# Sheet1.net
KiCad netlist of a schematic drawn in Altium Designer
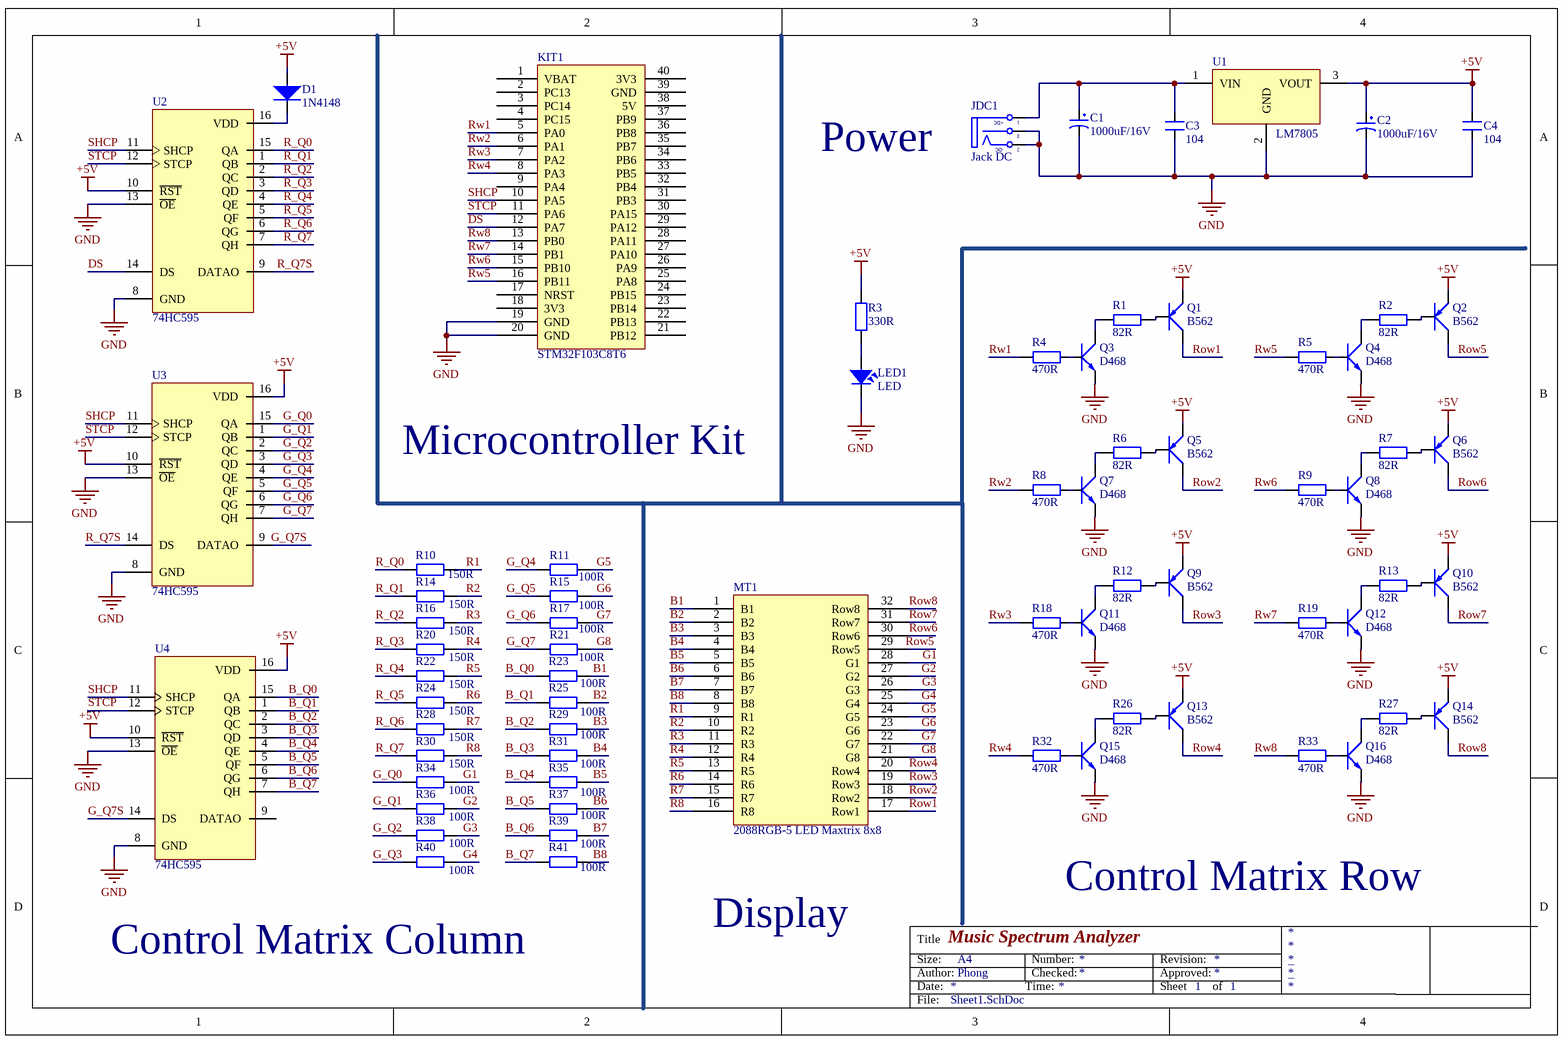
[diagram p0: Sheet1.SchDoc]

(export (version "E")
  (design (tool "Eeschema 10.0.6"))
  (components
    (comp (ref "C1")
      (value "1000uF/16V")
      (footprint "CP1.5/3.4")
      (description "Cap 1000uF/16V - 220uF/50V")
      (libsource (lib "KhanhBK_Library_4") (part "CP4"))
    )
    (comp (ref "C2")
      (value "1000uF/16V")
      (footprint "CP1.5/3.4")
      (description "Cap 1000uF/16V - 220uF/50V")
      (libsource (lib "KhanhBK_Library_4") (part "CP4"))
    )
    (comp (ref "C3")
      (value "104")
      (footprint "CN2")
      (description "Cap np 104 => 105pF")
      (libsource (lib "KhanhBK_SCH_Library_2") (part "CN2"))
    )
    (comp (ref "C4")
      (value "104")
      (footprint "CN2")
      (description "Cap np 104 => 105pF")
      (libsource (lib "KhanhBK_SCH_Library_2") (part "CN2"))
    )
    (comp (ref "D1")
      (value "1N4148")
      (footprint "DO-35")
      (description "Diode Standard")
      (fields (field (name "PART NUMBER") "LED 3 ly Single Colour"))
      (libsource (lib "KhanhBK_Library_4") (part "Diode Standard"))
    )
    (comp (ref "JDC1")
      (value "Jack DC")
      (footprint "DC-IN")
      (description "Jac DC input")
      (libsource (lib "KhanhBK_SCH_Library_2") (part "DCIN"))
    )
    (comp (ref "KIT1")
      (value "STM32F103C8T6")
      (footprint "STM32F103C8T6 BLUE PILL DEVELOPMENT BOARD")
      (description "STM32F103C8T6 Blue Pill Development Board")
      (libsource (lib "Schlib1") (part "Kit STM32F103C8T6 blue pill"))
    )
    (comp (ref "LED1")
      (value "LED")
      (footprint "LED-3")
      (description "LED Single colour Green and Red")
      (libsource (lib "KhanhBK_SCH_Library_2") (part "LED"))
    )
    (comp (ref "MT1")
      (value "2088RGB-5 LED Maxtrix 8x8")
      (footprint "LED 8x8 RGB")
      (description "32 pins")
      (libsource (lib "Schlib1") (part "LED 8x8 RGB"))
    )
    (comp (ref "Q1")
      (value "B562")
      (footprint "QTO-92")
      (description "P 600mW, ECB")
      (libsource (lib "KhanhBK_SCH_Library_2") (part "PNP_ECB"))
    )
    (comp (ref "Q2")
      (value "B562")
      (footprint "QTO-92")
      (description "P 600mW, ECB")
      (libsource (lib "KhanhBK_SCH_Library_2") (part "PNP_ECB"))
    )
    (comp (ref "Q3")
      (value "D468")
      (footprint "QTO-92")
      (description "P 600mW, ECB")
      (libsource (lib "KhanhBK_SCH_Library_2") (part "NPN_ECB"))
    )
    (comp (ref "Q4")
      (value "D468")
      (footprint "QTO-92")
      (description "P 600mW, ECB")
      (libsource (lib "KhanhBK_SCH_Library_2") (part "NPN_ECB"))
    )
    (comp (ref "Q5")
      (value "B562")
      (footprint "QTO-92")
      (description "P 600mW, ECB")
      (libsource (lib "KhanhBK_SCH_Library_2") (part "PNP_ECB"))
    )
    (comp (ref "Q6")
      (value "B562")
      (footprint "QTO-92")
      (description "P 600mW, ECB")
      (libsource (lib "KhanhBK_SCH_Library_2") (part "PNP_ECB"))
    )
    (comp (ref "Q7")
      (value "D468")
      (footprint "QTO-92")
      (description "P 600mW, ECB")
      (libsource (lib "KhanhBK_SCH_Library_2") (part "NPN_ECB"))
    )
    (comp (ref "Q8")
      (value "D468")
      (footprint "QTO-92")
      (description "P 600mW, ECB")
      (libsource (lib "KhanhBK_SCH_Library_2") (part "NPN_ECB"))
    )
    (comp (ref "Q9")
      (value "B562")
      (footprint "QTO-92")
      (description "P 600mW, ECB")
      (libsource (lib "KhanhBK_SCH_Library_2") (part "PNP_ECB"))
    )
    (comp (ref "Q10")
      (value "B562")
      (footprint "QTO-92")
      (description "P 600mW, ECB")
      (libsource (lib "KhanhBK_SCH_Library_2") (part "PNP_ECB"))
    )
    (comp (ref "Q11")
      (value "D468")
      (footprint "QTO-92")
      (description "P 600mW, ECB")
      (libsource (lib "KhanhBK_SCH_Library_2") (part "NPN_ECB"))
    )
    (comp (ref "Q12")
      (value "D468")
      (footprint "QTO-92")
      (description "P 600mW, ECB")
      (libsource (lib "KhanhBK_SCH_Library_2") (part "NPN_ECB"))
    )
    (comp (ref "Q13")
      (value "B562")
      (footprint "QTO-92")
      (description "P 600mW, ECB")
      (libsource (lib "KhanhBK_SCH_Library_2") (part "PNP_ECB"))
    )
    (comp (ref "Q14")
      (value "B562")
      (footprint "QTO-92")
      (description "P 600mW, ECB")
      (libsource (lib "KhanhBK_SCH_Library_2") (part "PNP_ECB"))
    )
    (comp (ref "Q15")
      (value "D468")
      (footprint "QTO-92")
      (description "P 600mW, ECB")
      (libsource (lib "KhanhBK_SCH_Library_2") (part "NPN_ECB"))
    )
    (comp (ref "Q16")
      (value "D468")
      (footprint "QTO-92")
      (description "P 600mW, ECB")
      (libsource (lib "KhanhBK_SCH_Library_2") (part "NPN_ECB"))
    )
    (comp (ref "R1")
      (value "82R")
      (footprint "RES-1/4W-SMALL")
      (description "Resistor 1/4W")
      (libsource (lib "KhanhBK_SCH_Library_2") (part "RES 1/4W"))
    )
    (comp (ref "R2")
      (value "82R")
      (footprint "RES-1/4W-SMALL")
      (description "Resistor 1/4W")
      (libsource (lib "KhanhBK_SCH_Library_2") (part "RES 1/4W"))
    )
    (comp (ref "R3")
      (value "330R")
      (footprint "RES-1/4W-SMALL")
      (description "Resistor 1/4W")
      (libsource (lib "KhanhBK_SCH_Library_2") (part "RES 1/4W"))
    )
    (comp (ref "R4")
      (value "470R")
      (footprint "RES-1/4W-SMALL")
      (description "Resistor 1/4W")
      (libsource (lib "KhanhBK_SCH_Library_2") (part "RES 1/4W"))
    )
    (comp (ref "R5")
      (value "470R")
      (footprint "RES-1/4W-SMALL")
      (description "Resistor 1/4W")
      (libsource (lib "KhanhBK_SCH_Library_2") (part "RES 1/4W"))
    )
    (comp (ref "R6")
      (value "82R")
      (footprint "RES-1/4W-SMALL")
      (description "Resistor 1/4W")
      (libsource (lib "KhanhBK_SCH_Library_2") (part "RES 1/4W"))
    )
    (comp (ref "R7")
      (value "82R")
      (footprint "RES-1/4W-SMALL")
      (description "Resistor 1/4W")
      (libsource (lib "KhanhBK_SCH_Library_2") (part "RES 1/4W"))
    )
    (comp (ref "R8")
      (value "470R")
      (footprint "RES-1/4W-SMALL")
      (description "Resistor 1/4W")
      (libsource (lib "KhanhBK_SCH_Library_2") (part "RES 1/4W"))
    )
    (comp (ref "R9")
      (value "470R")
      (footprint "RES-1/4W-SMALL")
      (description "Resistor 1/4W")
      (libsource (lib "KhanhBK_SCH_Library_2") (part "RES 1/4W"))
    )
    (comp (ref "R10")
      (value "150R")
      (footprint "RES-1/4W-SMALL")
      (description "Resistor 1/4W")
      (libsource (lib "KhanhBK_SCH_Library_2") (part "RES 1/4W"))
    )
    (comp (ref "R11")
      (value "100R")
      (footprint "RES-1/4W-SMALL")
      (description "Resistor 1/4W")
      (libsource (lib "KhanhBK_SCH_Library_2") (part "RES 1/4W"))
    )
    (comp (ref "R12")
      (value "82R")
      (footprint "RES-1/4W-SMALL")
      (description "Resistor 1/4W")
      (libsource (lib "KhanhBK_SCH_Library_2") (part "RES 1/4W"))
    )
    (comp (ref "R13")
      (value "82R")
      (footprint "RES-1/4W-SMALL")
      (description "Resistor 1/4W")
      (libsource (lib "KhanhBK_SCH_Library_2") (part "RES 1/4W"))
    )
    (comp (ref "R14")
      (value "150R")
      (footprint "RES-1/4W-SMALL")
      (description "Resistor 1/4W")
      (libsource (lib "KhanhBK_SCH_Library_2") (part "RES 1/4W"))
    )
    (comp (ref "R15")
      (value "100R")
      (footprint "RES-1/4W-SMALL")
      (description "Resistor 1/4W")
      (libsource (lib "KhanhBK_SCH_Library_2") (part "RES 1/4W"))
    )
    (comp (ref "R16")
      (value "150R")
      (footprint "RES-1/4W-SMALL")
      (description "Resistor 1/4W")
      (libsource (lib "KhanhBK_SCH_Library_2") (part "RES 1/4W"))
    )
    (comp (ref "R17")
      (value "100R")
      (footprint "RES-1/4W-SMALL")
      (description "Resistor 1/4W")
      (libsource (lib "KhanhBK_SCH_Library_2") (part "RES 1/4W"))
    )
    (comp (ref "R18")
      (value "470R")
      (footprint "RES-1/4W-SMALL")
      (description "Resistor 1/4W")
      (libsource (lib "KhanhBK_SCH_Library_2") (part "RES 1/4W"))
    )
    (comp (ref "R19")
      (value "470R")
      (footprint "RES-1/4W-SMALL")
      (description "Resistor 1/4W")
      (libsource (lib "KhanhBK_SCH_Library_2") (part "RES 1/4W"))
    )
    (comp (ref "R20")
      (value "150R")
      (footprint "RES-1/4W-SMALL")
      (description "Resistor 1/4W")
      (libsource (lib "KhanhBK_SCH_Library_2") (part "RES 1/4W"))
    )
    (comp (ref "R21")
      (value "100R")
      (footprint "RES-1/4W-SMALL")
      (description "Resistor 1/4W")
      (libsource (lib "KhanhBK_SCH_Library_2") (part "RES 1/4W"))
    )
    (comp (ref "R22")
      (value "150R")
      (footprint "RES-1/4W-SMALL")
      (description "Resistor 1/4W")
      (libsource (lib "KhanhBK_SCH_Library_2") (part "RES 1/4W"))
    )
    (comp (ref "R23")
      (value "100R")
      (footprint "RES-1/4W-SMALL")
      (description "Resistor 1/4W")
      (libsource (lib "KhanhBK_SCH_Library_2") (part "RES 1/4W"))
    )
    (comp (ref "R24")
      (value "150R")
      (footprint "RES-1/4W-SMALL")
      (description "Resistor 1/4W")
      (libsource (lib "KhanhBK_SCH_Library_2") (part "RES 1/4W"))
    )
    (comp (ref "R25")
      (value "100R")
      (footprint "RES-1/4W-SMALL")
      (description "Resistor 1/4W")
      (libsource (lib "KhanhBK_SCH_Library_2") (part "RES 1/4W"))
    )
    (comp (ref "R26")
      (value "82R")
      (footprint "RES-1/4W-SMALL")
      (description "Resistor 1/4W")
      (libsource (lib "KhanhBK_SCH_Library_2") (part "RES 1/4W"))
    )
    (comp (ref "R27")
      (value "82R")
      (footprint "RES-1/4W-SMALL")
      (description "Resistor 1/4W")
      (libsource (lib "KhanhBK_SCH_Library_2") (part "RES 1/4W"))
    )
    (comp (ref "R28")
      (value "150R")
      (footprint "RES-1/4W-SMALL")
      (description "Resistor 1/4W")
      (libsource (lib "KhanhBK_SCH_Library_2") (part "RES 1/4W"))
    )
    (comp (ref "R29")
      (value "100R")
      (footprint "RES-1/4W-SMALL")
      (description "Resistor 1/4W")
      (libsource (lib "KhanhBK_SCH_Library_2") (part "RES 1/4W"))
    )
    (comp (ref "R30")
      (value "150R")
      (footprint "RES-1/4W-SMALL")
      (description "Resistor 1/4W")
      (libsource (lib "KhanhBK_SCH_Library_2") (part "RES 1/4W"))
    )
    (comp (ref "R31")
      (value "100R")
      (footprint "RES-1/4W-SMALL")
      (description "Resistor 1/4W")
      (libsource (lib "KhanhBK_SCH_Library_2") (part "RES 1/4W"))
    )
    (comp (ref "R32")
      (value "470R")
      (footprint "RES-1/4W-SMALL")
      (description "Resistor 1/4W")
      (libsource (lib "KhanhBK_SCH_Library_2") (part "RES 1/4W"))
    )
    (comp (ref "R33")
      (value "470R")
      (footprint "RES-1/4W-SMALL")
      (description "Resistor 1/4W")
      (libsource (lib "KhanhBK_SCH_Library_2") (part "RES 1/4W"))
    )
    (comp (ref "R34")
      (value "100R")
      (footprint "RES-1/4W-SMALL")
      (description "Resistor 1/4W")
      (libsource (lib "KhanhBK_SCH_Library_2") (part "RES 1/4W"))
    )
    (comp (ref "R35")
      (value "100R")
      (footprint "RES-1/4W-SMALL")
      (description "Resistor 1/4W")
      (libsource (lib "KhanhBK_SCH_Library_2") (part "RES 1/4W"))
    )
    (comp (ref "R36")
      (value "100R")
      (footprint "RES-1/4W-SMALL")
      (description "Resistor 1/4W")
      (libsource (lib "KhanhBK_SCH_Library_2") (part "RES 1/4W"))
    )
    (comp (ref "R37")
      (value "100R")
      (footprint "RES-1/4W-SMALL")
      (description "Resistor 1/4W")
      (libsource (lib "KhanhBK_SCH_Library_2") (part "RES 1/4W"))
    )
    (comp (ref "R38")
      (value "100R")
      (footprint "RES-1/4W-SMALL")
      (description "Resistor 1/4W")
      (libsource (lib "KhanhBK_SCH_Library_2") (part "RES 1/4W"))
    )
    (comp (ref "R39")
      (value "100R")
      (footprint "RES-1/4W-SMALL")
      (description "Resistor 1/4W")
      (libsource (lib "KhanhBK_SCH_Library_2") (part "RES 1/4W"))
    )
    (comp (ref "R40")
      (value "100R")
      (footprint "RES-1/4W-SMALL")
      (description "Resistor 1/4W")
      (libsource (lib "KhanhBK_SCH_Library_2") (part "RES 1/4W"))
    )
    (comp (ref "R41")
      (value "100R")
      (footprint "RES-1/4W-SMALL")
      (description "Resistor 1/4W")
      (libsource (lib "KhanhBK_SCH_Library_2") (part "RES 1/4W"))
    )
    (comp (ref "U1")
      (value "LM7805")
      (footprint "Library:TO220H3")
      (libsource (lib "KhanhBK_SCH_Lib_5") (part "LM7815"))
    )
    (comp (ref "U2")
      (value "74HC595")
      (footprint "DIP16")
      (description "8-Bit Serial-Input/Serial or Prallel-Output Shift Register with Latched 3-State Outputs")
      (fields (field (name "PUBLISHER") "Altium Limited"))
      (libsource (lib "Devzone_SCHLib") (part "74HC595"))
    )
    (comp (ref "U3")
      (value "74HC595")
      (footprint "DIP16")
      (description "8-Bit Serial-Input/Serial or Prallel-Output Shift Register with Latched 3-State Outputs")
      (fields (field (name "PUBLISHER") "Altium Limited"))
      (libsource (lib "Devzone_SCHLib") (part "74HC595"))
    )
    (comp (ref "U4")
      (value "74HC595")
      (footprint "DIP16")
      (description "8-Bit Serial-Input/Serial or Prallel-Output Shift Register with Latched 3-State Outputs")
      (fields (field (name "PUBLISHER") "Altium Limited"))
      (libsource (lib "Devzone_SCHLib") (part "74HC595"))
    )
  )
  (nets
    (net (code "1") (name "+5V") (class "Default")
      (node (ref "C2") (pin "1") (pinfunction "1_1") (pintype "passive"))
      (node (ref "C4") (pin "2") (pinfunction "2_2") (pintype "passive"))
      (node (ref "D1") (pin "1") (pinfunction "1_1") (pintype "passive"))
      (node (ref "Q1") (pin "1") (pinfunction "E_1") (pintype "passive"))
      (node (ref "Q10") (pin "1") (pinfunction "E_1") (pintype "passive"))
      (node (ref "Q13") (pin "1") (pinfunction "E_1") (pintype "passive"))
      (node (ref "Q14") (pin "1") (pinfunction "E_1") (pintype "passive"))
      (node (ref "Q2") (pin "1") (pinfunction "E_1") (pintype "passive"))
      (node (ref "Q5") (pin "1") (pinfunction "E_1") (pintype "passive"))
      (node (ref "Q6") (pin "1") (pinfunction "E_1") (pintype "passive"))
      (node (ref "Q9") (pin "1") (pinfunction "E_1") (pintype "passive"))
      (node (ref "R3") (pin "2") (pinfunction "2_2") (pintype "passive"))
      (node (ref "U1") (pin "3") (pinfunction "VOUT_3") (pintype "passive"))
      (node (ref "U2") (pin "10") (pinfunction "~{RST}_10") (pintype "passive"))
      (node (ref "U3") (pin "10") (pinfunction "~{RST}_10") (pintype "passive"))
      (node (ref "U3") (pin "16") (pinfunction "VDD_16") (pintype "power_in"))
      (node (ref "U4") (pin "10") (pinfunction "~{RST}_10") (pintype "passive"))
      (node (ref "U4") (pin "16") (pinfunction "VDD_16") (pintype "power_in"))
    )
    (net (code "2") (name "/B1") (class "Default")
      (node (ref "MT1") (pin "1") (pinfunction "B1_1") (pintype "passive"))
      (node (ref "R23") (pin "2") (pinfunction "2_2") (pintype "passive"))
    )
    (net (code "3") (name "/B2") (class "Default")
      (node (ref "MT1") (pin "2") (pinfunction "B2_2") (pintype "passive"))
      (node (ref "R25") (pin "2") (pinfunction "2_2") (pintype "passive"))
    )
    (net (code "4") (name "/B3") (class "Default")
      (node (ref "MT1") (pin "3") (pinfunction "B3_3") (pintype "passive"))
      (node (ref "R29") (pin "2") (pinfunction "2_2") (pintype "passive"))
    )
    (net (code "5") (name "/B4") (class "Default")
      (node (ref "MT1") (pin "4") (pinfunction "B4_4") (pintype "passive"))
      (node (ref "R31") (pin "2") (pinfunction "2_2") (pintype "passive"))
    )
    (net (code "6") (name "/B5") (class "Default")
      (node (ref "MT1") (pin "5") (pinfunction "B5_5") (pintype "passive"))
      (node (ref "R35") (pin "2") (pinfunction "2_2") (pintype "passive"))
    )
    (net (code "7") (name "/B6") (class "Default")
      (node (ref "MT1") (pin "6") (pinfunction "B6_6") (pintype "passive"))
      (node (ref "R37") (pin "2") (pinfunction "2_2") (pintype "passive"))
    )
    (net (code "8") (name "/B7") (class "Default")
      (node (ref "MT1") (pin "7") (pinfunction "B7_7") (pintype "passive"))
      (node (ref "R39") (pin "2") (pinfunction "2_2") (pintype "passive"))
    )
    (net (code "9") (name "/B8") (class "Default")
      (node (ref "MT1") (pin "8") (pinfunction "B8_8") (pintype "passive"))
      (node (ref "R41") (pin "2") (pinfunction "2_2") (pintype "passive"))
    )
    (net (code "10") (name "/B_Q0") (class "Default")
      (node (ref "R23") (pin "1") (pinfunction "1_1") (pintype "passive"))
      (node (ref "U4") (pin "15") (pinfunction "QA_15") (pintype "passive"))
    )
    (net (code "11") (name "/B_Q1") (class "Default")
      (node (ref "R25") (pin "1") (pinfunction "1_1") (pintype "passive"))
      (node (ref "U4") (pin "1") (pinfunction "QB_1") (pintype "passive"))
    )
    (net (code "12") (name "/B_Q2") (class "Default")
      (node (ref "R29") (pin "1") (pinfunction "1_1") (pintype "passive"))
      (node (ref "U4") (pin "2") (pinfunction "QC_2") (pintype "passive"))
    )
    (net (code "13") (name "/B_Q3") (class "Default")
      (node (ref "R31") (pin "1") (pinfunction "1_1") (pintype "passive"))
      (node (ref "U4") (pin "3") (pinfunction "QD_3") (pintype "passive"))
    )
    (net (code "14") (name "/B_Q4") (class "Default")
      (node (ref "R35") (pin "1") (pinfunction "1_1") (pintype "passive"))
      (node (ref "U4") (pin "4") (pinfunction "QE_4") (pintype "passive"))
    )
    (net (code "15") (name "/B_Q5") (class "Default")
      (node (ref "R37") (pin "1") (pinfunction "1_1") (pintype "passive"))
      (node (ref "U4") (pin "5") (pinfunction "QF_5") (pintype "passive"))
    )
    (net (code "16") (name "/B_Q6") (class "Default")
      (node (ref "R39") (pin "1") (pinfunction "1_1") (pintype "passive"))
      (node (ref "U4") (pin "6") (pinfunction "QG_6") (pintype "passive"))
    )
    (net (code "17") (name "/B_Q7") (class "Default")
      (node (ref "R41") (pin "1") (pinfunction "1_1") (pintype "passive"))
      (node (ref "U4") (pin "7") (pinfunction "QH_7") (pintype "passive"))
    )
    (net (code "18") (name "/DS") (class "Default")
      (node (ref "KIT1") (pin "12") (pinfunction "PA7_12") (pintype "passive"))
      (node (ref "U2") (pin "14") (pinfunction "DS_14") (pintype "passive"))
    )
    (net (code "19") (name "/G1") (class "Default")
      (node (ref "MT1") (pin "28") (pinfunction "G1_28") (pintype "passive"))
      (node (ref "R34") (pin "2") (pinfunction "2_2") (pintype "passive"))
    )
    (net (code "20") (name "/G2") (class "Default")
      (node (ref "MT1") (pin "27") (pinfunction "G2_27") (pintype "passive"))
      (node (ref "R36") (pin "2") (pinfunction "2_2") (pintype "passive"))
    )
    (net (code "21") (name "/G3") (class "Default")
      (node (ref "MT1") (pin "26") (pinfunction "G3_26") (pintype "passive"))
      (node (ref "R38") (pin "2") (pinfunction "2_2") (pintype "passive"))
    )
    (net (code "22") (name "/G4") (class "Default")
      (node (ref "MT1") (pin "25") (pinfunction "G4_25") (pintype "passive"))
      (node (ref "R40") (pin "2") (pinfunction "2_2") (pintype "passive"))
    )
    (net (code "23") (name "/G5") (class "Default")
      (node (ref "MT1") (pin "24") (pinfunction "G5_24") (pintype "passive"))
      (node (ref "R11") (pin "2") (pinfunction "2_2") (pintype "passive"))
    )
    (net (code "24") (name "/G6") (class "Default")
      (node (ref "MT1") (pin "23") (pinfunction "G6_23") (pintype "passive"))
      (node (ref "R15") (pin "2") (pinfunction "2_2") (pintype "passive"))
    )
    (net (code "25") (name "/G7") (class "Default")
      (node (ref "MT1") (pin "22") (pinfunction "G7_22") (pintype "passive"))
      (node (ref "R17") (pin "2") (pinfunction "2_2") (pintype "passive"))
    )
    (net (code "26") (name "/G8") (class "Default")
      (node (ref "MT1") (pin "21") (pinfunction "G8_21") (pintype "passive"))
      (node (ref "R21") (pin "2") (pinfunction "2_2") (pintype "passive"))
    )
    (net (code "27") (name "/G_Q0") (class "Default")
      (node (ref "R34") (pin "1") (pinfunction "1_1") (pintype "passive"))
      (node (ref "U3") (pin "15") (pinfunction "QA_15") (pintype "passive"))
    )
    (net (code "28") (name "/G_Q1") (class "Default")
      (node (ref "R36") (pin "1") (pinfunction "1_1") (pintype "passive"))
      (node (ref "U3") (pin "1") (pinfunction "QB_1") (pintype "passive"))
    )
    (net (code "29") (name "/G_Q2") (class "Default")
      (node (ref "R38") (pin "1") (pinfunction "1_1") (pintype "passive"))
      (node (ref "U3") (pin "2") (pinfunction "QC_2") (pintype "passive"))
    )
    (net (code "30") (name "/G_Q3") (class "Default")
      (node (ref "R40") (pin "1") (pinfunction "1_1") (pintype "passive"))
      (node (ref "U3") (pin "3") (pinfunction "QD_3") (pintype "passive"))
    )
    (net (code "31") (name "/G_Q4") (class "Default")
      (node (ref "R11") (pin "1") (pinfunction "1_1") (pintype "passive"))
      (node (ref "U3") (pin "4") (pinfunction "QE_4") (pintype "passive"))
    )
    (net (code "32") (name "/G_Q5") (class "Default")
      (node (ref "R15") (pin "1") (pinfunction "1_1") (pintype "passive"))
      (node (ref "U3") (pin "5") (pinfunction "QF_5") (pintype "passive"))
    )
    (net (code "33") (name "/G_Q6") (class "Default")
      (node (ref "R17") (pin "1") (pinfunction "1_1") (pintype "passive"))
      (node (ref "U3") (pin "6") (pinfunction "QG_6") (pintype "passive"))
    )
    (net (code "34") (name "/G_Q7") (class "Default")
      (node (ref "R21") (pin "1") (pinfunction "1_1") (pintype "passive"))
      (node (ref "U3") (pin "7") (pinfunction "QH_7") (pintype "passive"))
    )
    (net (code "35") (name "/G_Q7S") (class "Default")
      (node (ref "U3") (pin "9") (pinfunction "DATAO_9") (pintype "passive"))
      (node (ref "U4") (pin "14") (pinfunction "DS_14") (pintype "passive"))
    )
    (net (code "36") (name "/R1") (class "Default")
      (node (ref "MT1") (pin "9") (pinfunction "R1_9") (pintype "passive"))
      (node (ref "R10") (pin "2") (pinfunction "2_2") (pintype "passive"))
    )
    (net (code "37") (name "/R2") (class "Default")
      (node (ref "MT1") (pin "10") (pinfunction "R2_10") (pintype "passive"))
      (node (ref "R14") (pin "2") (pinfunction "2_2") (pintype "passive"))
    )
    (net (code "38") (name "/R3") (class "Default")
      (node (ref "MT1") (pin "11") (pinfunction "R3_11") (pintype "passive"))
      (node (ref "R16") (pin "2") (pinfunction "2_2") (pintype "passive"))
    )
    (net (code "39") (name "/R4") (class "Default")
      (node (ref "MT1") (pin "12") (pinfunction "R4_12") (pintype "passive"))
      (node (ref "R20") (pin "2") (pinfunction "2_2") (pintype "passive"))
    )
    (net (code "40") (name "/R5") (class "Default")
      (node (ref "MT1") (pin "13") (pinfunction "R5_13") (pintype "passive"))
      (node (ref "R22") (pin "2") (pinfunction "2_2") (pintype "passive"))
    )
    (net (code "41") (name "/R6") (class "Default")
      (node (ref "MT1") (pin "14") (pinfunction "R6_14") (pintype "passive"))
      (node (ref "R24") (pin "2") (pinfunction "2_2") (pintype "passive"))
    )
    (net (code "42") (name "/R7") (class "Default")
      (node (ref "MT1") (pin "15") (pinfunction "R7_15") (pintype "passive"))
      (node (ref "R28") (pin "2") (pinfunction "2_2") (pintype "passive"))
    )
    (net (code "43") (name "/R8") (class "Default")
      (node (ref "MT1") (pin "16") (pinfunction "R8_16") (pintype "passive"))
      (node (ref "R30") (pin "2") (pinfunction "2_2") (pintype "passive"))
    )
    (net (code "44") (name "/R_Q0") (class "Default")
      (node (ref "R10") (pin "1") (pinfunction "1_1") (pintype "passive"))
      (node (ref "U2") (pin "15") (pinfunction "QA_15") (pintype "passive"))
    )
    (net (code "45") (name "/R_Q1") (class "Default")
      (node (ref "R14") (pin "1") (pinfunction "1_1") (pintype "passive"))
      (node (ref "U2") (pin "1") (pinfunction "QB_1") (pintype "passive"))
    )
    (net (code "46") (name "/R_Q2") (class "Default")
      (node (ref "R16") (pin "1") (pinfunction "1_1") (pintype "passive"))
      (node (ref "U2") (pin "2") (pinfunction "QC_2") (pintype "passive"))
    )
    (net (code "47") (name "/R_Q3") (class "Default")
      (node (ref "R20") (pin "1") (pinfunction "1_1") (pintype "passive"))
      (node (ref "U2") (pin "3") (pinfunction "QD_3") (pintype "passive"))
    )
    (net (code "48") (name "/R_Q4") (class "Default")
      (node (ref "R22") (pin "1") (pinfunction "1_1") (pintype "passive"))
      (node (ref "U2") (pin "4") (pinfunction "QE_4") (pintype "passive"))
    )
    (net (code "49") (name "/R_Q5") (class "Default")
      (node (ref "R24") (pin "1") (pinfunction "1_1") (pintype "passive"))
      (node (ref "U2") (pin "5") (pinfunction "QF_5") (pintype "passive"))
    )
    (net (code "50") (name "/R_Q6") (class "Default")
      (node (ref "R28") (pin "1") (pinfunction "1_1") (pintype "passive"))
      (node (ref "U2") (pin "6") (pinfunction "QG_6") (pintype "passive"))
    )
    (net (code "51") (name "/R_Q7") (class "Default")
      (node (ref "R30") (pin "1") (pinfunction "1_1") (pintype "passive"))
      (node (ref "U2") (pin "7") (pinfunction "QH_7") (pintype "passive"))
    )
    (net (code "52") (name "/R_Q7S") (class "Default")
      (node (ref "U2") (pin "9") (pinfunction "DATAO_9") (pintype "passive"))
      (node (ref "U3") (pin "14") (pinfunction "DS_14") (pintype "passive"))
    )
    (net (code "53") (name "/Row1") (class "Default")
      (node (ref "MT1") (pin "17") (pinfunction "Row1_17") (pintype "passive"))
      (node (ref "Q1") (pin "2") (pinfunction "C_2") (pintype "passive"))
    )
    (net (code "54") (name "/Row2") (class "Default")
      (node (ref "MT1") (pin "18") (pinfunction "Row2_18") (pintype "passive"))
      (node (ref "Q5") (pin "2") (pinfunction "C_2") (pintype "passive"))
    )
    (net (code "55") (name "/Row3") (class "Default")
      (node (ref "MT1") (pin "19") (pinfunction "Row3_19") (pintype "passive"))
      (node (ref "Q9") (pin "2") (pinfunction "C_2") (pintype "passive"))
    )
    (net (code "56") (name "/Row4") (class "Default")
      (node (ref "MT1") (pin "20") (pinfunction "Row4_20") (pintype "passive"))
      (node (ref "Q13") (pin "2") (pinfunction "C_2") (pintype "passive"))
    )
    (net (code "57") (name "/Row5") (class "Default")
      (node (ref "MT1") (pin "29") (pinfunction "Row5_29") (pintype "passive"))
      (node (ref "Q2") (pin "2") (pinfunction "C_2") (pintype "passive"))
    )
    (net (code "58") (name "/Row6") (class "Default")
      (node (ref "MT1") (pin "30") (pinfunction "Row6_30") (pintype "passive"))
      (node (ref "Q6") (pin "2") (pinfunction "C_2") (pintype "passive"))
    )
    (net (code "59") (name "/Row7") (class "Default")
      (node (ref "MT1") (pin "31") (pinfunction "Row7_31") (pintype "passive"))
      (node (ref "Q10") (pin "2") (pinfunction "C_2") (pintype "passive"))
    )
    (net (code "60") (name "/Row8") (class "Default")
      (node (ref "MT1") (pin "32") (pinfunction "Row8_32") (pintype "passive"))
      (node (ref "Q14") (pin "2") (pinfunction "C_2") (pintype "passive"))
    )
    (net (code "61") (name "/Rw1") (class "Default")
      (node (ref "KIT1") (pin "5") (pinfunction "PA0_5") (pintype "passive"))
      (node (ref "R4") (pin "1") (pinfunction "1_1") (pintype "passive"))
    )
    (net (code "62") (name "/Rw2") (class "Default")
      (node (ref "KIT1") (pin "6") (pinfunction "PA1_6") (pintype "passive"))
      (node (ref "R8") (pin "1") (pinfunction "1_1") (pintype "passive"))
    )
    (net (code "63") (name "/Rw3") (class "Default")
      (node (ref "KIT1") (pin "7") (pinfunction "PA2_7") (pintype "passive"))
      (node (ref "R18") (pin "1") (pinfunction "1_1") (pintype "passive"))
    )
    (net (code "64") (name "/Rw4") (class "Default")
      (node (ref "KIT1") (pin "8") (pinfunction "PA3_8") (pintype "passive"))
      (node (ref "R32") (pin "1") (pinfunction "1_1") (pintype "passive"))
    )
    (net (code "65") (name "/Rw5") (class "Default")
      (node (ref "KIT1") (pin "16") (pinfunction "PB11_16") (pintype "passive"))
      (node (ref "R5") (pin "1") (pinfunction "1_1") (pintype "passive"))
    )
    (net (code "66") (name "/Rw6") (class "Default")
      (node (ref "KIT1") (pin "15") (pinfunction "PB10_15") (pintype "passive"))
      (node (ref "R9") (pin "1") (pinfunction "1_1") (pintype "passive"))
    )
    (net (code "67") (name "/Rw7") (class "Default")
      (node (ref "KIT1") (pin "14") (pinfunction "PB1_14") (pintype "passive"))
      (node (ref "R19") (pin "1") (pinfunction "1_1") (pintype "passive"))
    )
    (net (code "68") (name "/Rw8") (class "Default")
      (node (ref "KIT1") (pin "13") (pinfunction "PB0_13") (pintype "passive"))
      (node (ref "R33") (pin "1") (pinfunction "1_1") (pintype "passive"))
    )
    (net (code "69") (name "/SHCP") (class "Default")
      (node (ref "KIT1") (pin "10") (pinfunction "PA5_10") (pintype "passive"))
      (node (ref "U2") (pin "11") (pinfunction "SHCP_11") (pintype "passive"))
      (node (ref "U3") (pin "11") (pinfunction "SHCP_11") (pintype "passive"))
      (node (ref "U4") (pin "11") (pinfunction "SHCP_11") (pintype "passive"))
    )
    (net (code "70") (name "/STCP") (class "Default")
      (node (ref "KIT1") (pin "11") (pinfunction "PA6_11") (pintype "passive"))
      (node (ref "U2") (pin "12") (pinfunction "STCP_12") (pintype "passive"))
      (node (ref "U3") (pin "12") (pinfunction "STCP_12") (pintype "passive"))
      (node (ref "U4") (pin "12") (pinfunction "STCP_12") (pintype "passive"))
    )
    (net (code "71") (name "GND") (class "Default")
      (node (ref "C1") (pin "2") (pinfunction "2_2") (pintype "passive"))
      (node (ref "C2") (pin "2") (pinfunction "2_2") (pintype "passive"))
      (node (ref "C3") (pin "1") (pinfunction "1_1") (pintype "passive"))
      (node (ref "C4") (pin "1") (pinfunction "1_1") (pintype "passive"))
      (node (ref "JDC1") (pin "2") (pinfunction "TN_2") (pintype "passive"))
      (node (ref "JDC1") (pin "3") (pinfunction "S_3") (pintype "power_in"))
      (node (ref "KIT1") (pin "19") (pinfunction "GND_19") (pintype "passive"))
      (node (ref "KIT1") (pin "20") (pinfunction "GND_20") (pintype "passive"))
      (node (ref "LED1") (pin "2") (pinfunction "2_2") (pintype "passive"))
      (node (ref "Q11") (pin "1") (pinfunction "E_1") (pintype "passive"))
      (node (ref "Q12") (pin "1") (pinfunction "E_1") (pintype "passive"))
      (node (ref "Q15") (pin "1") (pinfunction "E_1") (pintype "passive"))
      (node (ref "Q16") (pin "1") (pinfunction "E_1") (pintype "passive"))
      (node (ref "Q3") (pin "1") (pinfunction "E_1") (pintype "passive"))
      (node (ref "Q4") (pin "1") (pinfunction "E_1") (pintype "passive"))
      (node (ref "Q7") (pin "1") (pinfunction "E_1") (pintype "passive"))
      (node (ref "Q8") (pin "1") (pinfunction "E_1") (pintype "passive"))
      (node (ref "U1") (pin "2") (pinfunction "GND_2") (pintype "passive"))
      (node (ref "U2") (pin "13") (pinfunction "~{OE}_13") (pintype "passive"))
      (node (ref "U2") (pin "8") (pinfunction "GND_8") (pintype "power_in"))
      (node (ref "U3") (pin "13") (pinfunction "~{OE}_13") (pintype "passive"))
      (node (ref "U3") (pin "8") (pinfunction "GND_8") (pintype "power_in"))
      (node (ref "U4") (pin "13") (pinfunction "~{OE}_13") (pintype "passive"))
      (node (ref "U4") (pin "8") (pinfunction "GND_8") (pintype "power_in"))
    )
    (net (code "72") (name "Net-(JDC1-T)") (class "Default")
      (node (ref "C1") (pin "1") (pinfunction "1_1") (pintype "passive"))
      (node (ref "C3") (pin "2") (pinfunction "2_2") (pintype "passive"))
      (node (ref "JDC1") (pin "1") (pinfunction "T_1") (pintype "passive"))
      (node (ref "U1") (pin "1") (pinfunction "VIN_1") (pintype "passive"))
    )
    (net (code "73") (name "Net-(LED1-Pad1)") (class "Default")
      (node (ref "LED1") (pin "1") (pinfunction "1_1") (pintype "passive"))
      (node (ref "R3") (pin "1") (pinfunction "1_1") (pintype "passive"))
    )
    (net (code "74") (name "Net-(Q1-B)") (class "Default")
      (node (ref "Q1") (pin "3") (pinfunction "B_3") (pintype "passive"))
      (node (ref "R1") (pin "2") (pinfunction "2_2") (pintype "passive"))
    )
    (net (code "75") (name "Net-(Q2-B)") (class "Default")
      (node (ref "Q2") (pin "3") (pinfunction "B_3") (pintype "passive"))
      (node (ref "R2") (pin "2") (pinfunction "2_2") (pintype "passive"))
    )
    (net (code "76") (name "Net-(Q3-B)") (class "Default")
      (node (ref "Q3") (pin "3") (pinfunction "B_3") (pintype "passive"))
      (node (ref "R4") (pin "2") (pinfunction "2_2") (pintype "passive"))
    )
    (net (code "77") (name "Net-(Q3-C)") (class "Default")
      (node (ref "Q3") (pin "2") (pinfunction "C_2") (pintype "passive"))
      (node (ref "R1") (pin "1") (pinfunction "1_1") (pintype "passive"))
    )
    (net (code "78") (name "Net-(Q4-B)") (class "Default")
      (node (ref "Q4") (pin "3") (pinfunction "B_3") (pintype "passive"))
      (node (ref "R5") (pin "2") (pinfunction "2_2") (pintype "passive"))
    )
    (net (code "79") (name "Net-(Q4-C)") (class "Default")
      (node (ref "Q4") (pin "2") (pinfunction "C_2") (pintype "passive"))
      (node (ref "R2") (pin "1") (pinfunction "1_1") (pintype "passive"))
    )
    (net (code "80") (name "Net-(Q5-B)") (class "Default")
      (node (ref "Q5") (pin "3") (pinfunction "B_3") (pintype "passive"))
      (node (ref "R6") (pin "2") (pinfunction "2_2") (pintype "passive"))
    )
    (net (code "81") (name "Net-(Q6-B)") (class "Default")
      (node (ref "Q6") (pin "3") (pinfunction "B_3") (pintype "passive"))
      (node (ref "R7") (pin "2") (pinfunction "2_2") (pintype "passive"))
    )
    (net (code "82") (name "Net-(Q7-B)") (class "Default")
      (node (ref "Q7") (pin "3") (pinfunction "B_3") (pintype "passive"))
      (node (ref "R8") (pin "2") (pinfunction "2_2") (pintype "passive"))
    )
    (net (code "83") (name "Net-(Q7-C)") (class "Default")
      (node (ref "Q7") (pin "2") (pinfunction "C_2") (pintype "passive"))
      (node (ref "R6") (pin "1") (pinfunction "1_1") (pintype "passive"))
    )
    (net (code "84") (name "Net-(Q8-B)") (class "Default")
      (node (ref "Q8") (pin "3") (pinfunction "B_3") (pintype "passive"))
      (node (ref "R9") (pin "2") (pinfunction "2_2") (pintype "passive"))
    )
    (net (code "85") (name "Net-(Q8-C)") (class "Default")
      (node (ref "Q8") (pin "2") (pinfunction "C_2") (pintype "passive"))
      (node (ref "R7") (pin "1") (pinfunction "1_1") (pintype "passive"))
    )
    (net (code "86") (name "Net-(Q9-B)") (class "Default")
      (node (ref "Q9") (pin "3") (pinfunction "B_3") (pintype "passive"))
      (node (ref "R12") (pin "2") (pinfunction "2_2") (pintype "passive"))
    )
    (net (code "87") (name "Net-(Q10-B)") (class "Default")
      (node (ref "Q10") (pin "3") (pinfunction "B_3") (pintype "passive"))
      (node (ref "R13") (pin "2") (pinfunction "2_2") (pintype "passive"))
    )
    (net (code "88") (name "Net-(Q11-B)") (class "Default")
      (node (ref "Q11") (pin "3") (pinfunction "B_3") (pintype "passive"))
      (node (ref "R18") (pin "2") (pinfunction "2_2") (pintype "passive"))
    )
    (net (code "89") (name "Net-(Q11-C)") (class "Default")
      (node (ref "Q11") (pin "2") (pinfunction "C_2") (pintype "passive"))
      (node (ref "R12") (pin "1") (pinfunction "1_1") (pintype "passive"))
    )
    (net (code "90") (name "Net-(Q12-B)") (class "Default")
      (node (ref "Q12") (pin "3") (pinfunction "B_3") (pintype "passive"))
      (node (ref "R19") (pin "2") (pinfunction "2_2") (pintype "passive"))
    )
    (net (code "91") (name "Net-(Q12-C)") (class "Default")
      (node (ref "Q12") (pin "2") (pinfunction "C_2") (pintype "passive"))
      (node (ref "R13") (pin "1") (pinfunction "1_1") (pintype "passive"))
    )
    (net (code "92") (name "Net-(Q13-B)") (class "Default")
      (node (ref "Q13") (pin "3") (pinfunction "B_3") (pintype "passive"))
      (node (ref "R26") (pin "2") (pinfunction "2_2") (pintype "passive"))
    )
    (net (code "93") (name "Net-(Q14-B)") (class "Default")
      (node (ref "Q14") (pin "3") (pinfunction "B_3") (pintype "passive"))
      (node (ref "R27") (pin "2") (pinfunction "2_2") (pintype "passive"))
    )
    (net (code "94") (name "Net-(Q15-B)") (class "Default")
      (node (ref "Q15") (pin "3") (pinfunction "B_3") (pintype "passive"))
      (node (ref "R32") (pin "2") (pinfunction "2_2") (pintype "passive"))
    )
    (net (code "95") (name "Net-(Q15-C)") (class "Default")
      (node (ref "Q15") (pin "2") (pinfunction "C_2") (pintype "passive"))
      (node (ref "R26") (pin "1") (pinfunction "1_1") (pintype "passive"))
    )
    (net (code "96") (name "Net-(Q16-B)") (class "Default")
      (node (ref "Q16") (pin "3") (pinfunction "B_3") (pintype "passive"))
      (node (ref "R33") (pin "2") (pinfunction "2_2") (pintype "passive"))
    )
    (net (code "97") (name "Net-(Q16-C)") (class "Default")
      (node (ref "Q16") (pin "2") (pinfunction "C_2") (pintype "passive"))
      (node (ref "R27") (pin "1") (pinfunction "1_1") (pintype "passive"))
    )
    (net (code "98") (name "Net-(U2-VDD)") (class "Default")
      (node (ref "D1") (pin "2") (pinfunction "2_2") (pintype "passive"))
      (node (ref "U2") (pin "16") (pinfunction "VDD_16") (pintype "power_in"))
    )
    (net (code "99") (name "unconnected-(KIT1-3V3-Pad18)") (class "Default")
      (node (ref "KIT1") (pin "18") (pinfunction "3V3_18") (pintype "passive"))
    )
    (net (code "100") (name "unconnected-(KIT1-3V3-Pad40)") (class "Default")
      (node (ref "KIT1") (pin "40") (pinfunction "3V3_40") (pintype "passive"))
    )
    (net (code "101") (name "unconnected-(KIT1-5V-Pad38)") (class "Default")
      (node (ref "KIT1") (pin "38") (pinfunction "5V_38") (pintype "passive"))
    )
    (net (code "102") (name "unconnected-(KIT1-GND-Pad39)") (class "Default")
      (node (ref "KIT1") (pin "39") (pinfunction "GND_39") (pintype "passive"))
    )
    (net (code "103") (name "unconnected-(KIT1-NRST-Pad17)") (class "Default")
      (node (ref "KIT1") (pin "17") (pinfunction "NRST_17") (pintype "passive"))
    )
    (net (code "104") (name "unconnected-(KIT1-PA4-Pad9)") (class "Default")
      (node (ref "KIT1") (pin "9") (pinfunction "PA4_9") (pintype "passive"))
    )
    (net (code "105") (name "unconnected-(KIT1-PA8-Pad25)") (class "Default")
      (node (ref "KIT1") (pin "25") (pinfunction "PA8_25") (pintype "passive"))
    )
    (net (code "106") (name "unconnected-(KIT1-PA9-Pad26)") (class "Default")
      (node (ref "KIT1") (pin "26") (pinfunction "PA9_26") (pintype "passive"))
    )
    (net (code "107") (name "unconnected-(KIT1-PA10-Pad27)") (class "Default")
      (node (ref "KIT1") (pin "27") (pinfunction "PA10_27") (pintype "passive"))
    )
    (net (code "108") (name "unconnected-(KIT1-PA11-Pad28)") (class "Default")
      (node (ref "KIT1") (pin "28") (pinfunction "PA11_28") (pintype "passive"))
    )
    (net (code "109") (name "unconnected-(KIT1-PA12-Pad29)") (class "Default")
      (node (ref "KIT1") (pin "29") (pinfunction "PA12_29") (pintype "passive"))
    )
    (net (code "110") (name "unconnected-(KIT1-PA15-Pad30)") (class "Default")
      (node (ref "KIT1") (pin "30") (pinfunction "PA15_30") (pintype "passive"))
    )
    (net (code "111") (name "unconnected-(KIT1-PB3-Pad31)") (class "Default")
      (node (ref "KIT1") (pin "31") (pinfunction "PB3_31") (pintype "passive"))
    )
    (net (code "112") (name "unconnected-(KIT1-PB4-Pad32)") (class "Default")
      (node (ref "KIT1") (pin "32") (pinfunction "PB4_32") (pintype "passive"))
    )
    (net (code "113") (name "unconnected-(KIT1-PB5-Pad33)") (class "Default")
      (node (ref "KIT1") (pin "33") (pinfunction "PB5_33") (pintype "passive"))
    )
    (net (code "114") (name "unconnected-(KIT1-PB6-Pad34)") (class "Default")
      (node (ref "KIT1") (pin "34") (pinfunction "PB6_34") (pintype "passive"))
    )
    (net (code "115") (name "unconnected-(KIT1-PB7-Pad35)") (class "Default")
      (node (ref "KIT1") (pin "35") (pinfunction "PB7_35") (pintype "passive"))
    )
    (net (code "116") (name "unconnected-(KIT1-PB8-Pad36)") (class "Default")
      (node (ref "KIT1") (pin "36") (pinfunction "PB8_36") (pintype "passive"))
    )
    (net (code "117") (name "unconnected-(KIT1-PB9-Pad37)") (class "Default")
      (node (ref "KIT1") (pin "37") (pinfunction "PB9_37") (pintype "passive"))
    )
    (net (code "118") (name "unconnected-(KIT1-PB12-Pad21)") (class "Default")
      (node (ref "KIT1") (pin "21") (pinfunction "PB12_21") (pintype "passive"))
    )
    (net (code "119") (name "unconnected-(KIT1-PB13-Pad22)") (class "Default")
      (node (ref "KIT1") (pin "22") (pinfunction "PB13_22") (pintype "passive"))
    )
    (net (code "120") (name "unconnected-(KIT1-PB14-Pad23)") (class "Default")
      (node (ref "KIT1") (pin "23") (pinfunction "PB14_23") (pintype "passive"))
    )
    (net (code "121") (name "unconnected-(KIT1-PB15-Pad24)") (class "Default")
      (node (ref "KIT1") (pin "24") (pinfunction "PB15_24") (pintype "passive"))
    )
    (net (code "122") (name "unconnected-(KIT1-PC13-Pad2)") (class "Default")
      (node (ref "KIT1") (pin "2") (pinfunction "PC13_2") (pintype "passive"))
    )
    (net (code "123") (name "unconnected-(KIT1-PC14-Pad3)") (class "Default")
      (node (ref "KIT1") (pin "3") (pinfunction "PC14_3") (pintype "passive"))
    )
    (net (code "124") (name "unconnected-(KIT1-PC15-Pad4)") (class "Default")
      (node (ref "KIT1") (pin "4") (pinfunction "PC15_4") (pintype "passive"))
    )
    (net (code "125") (name "unconnected-(KIT1-VBAT-Pad1)") (class "Default")
      (node (ref "KIT1") (pin "1") (pinfunction "VBAT_1") (pintype "passive"))
    )
    (net (code "126") (name "unconnected-(U4-DATAO-Pad9)") (class "Default")
      (node (ref "U4") (pin "9") (pinfunction "DATAO_9") (pintype "passive"))
    )
  )
)
